# rev02_19.net
KiCad netlist of a schematic drawn in Altium Designer
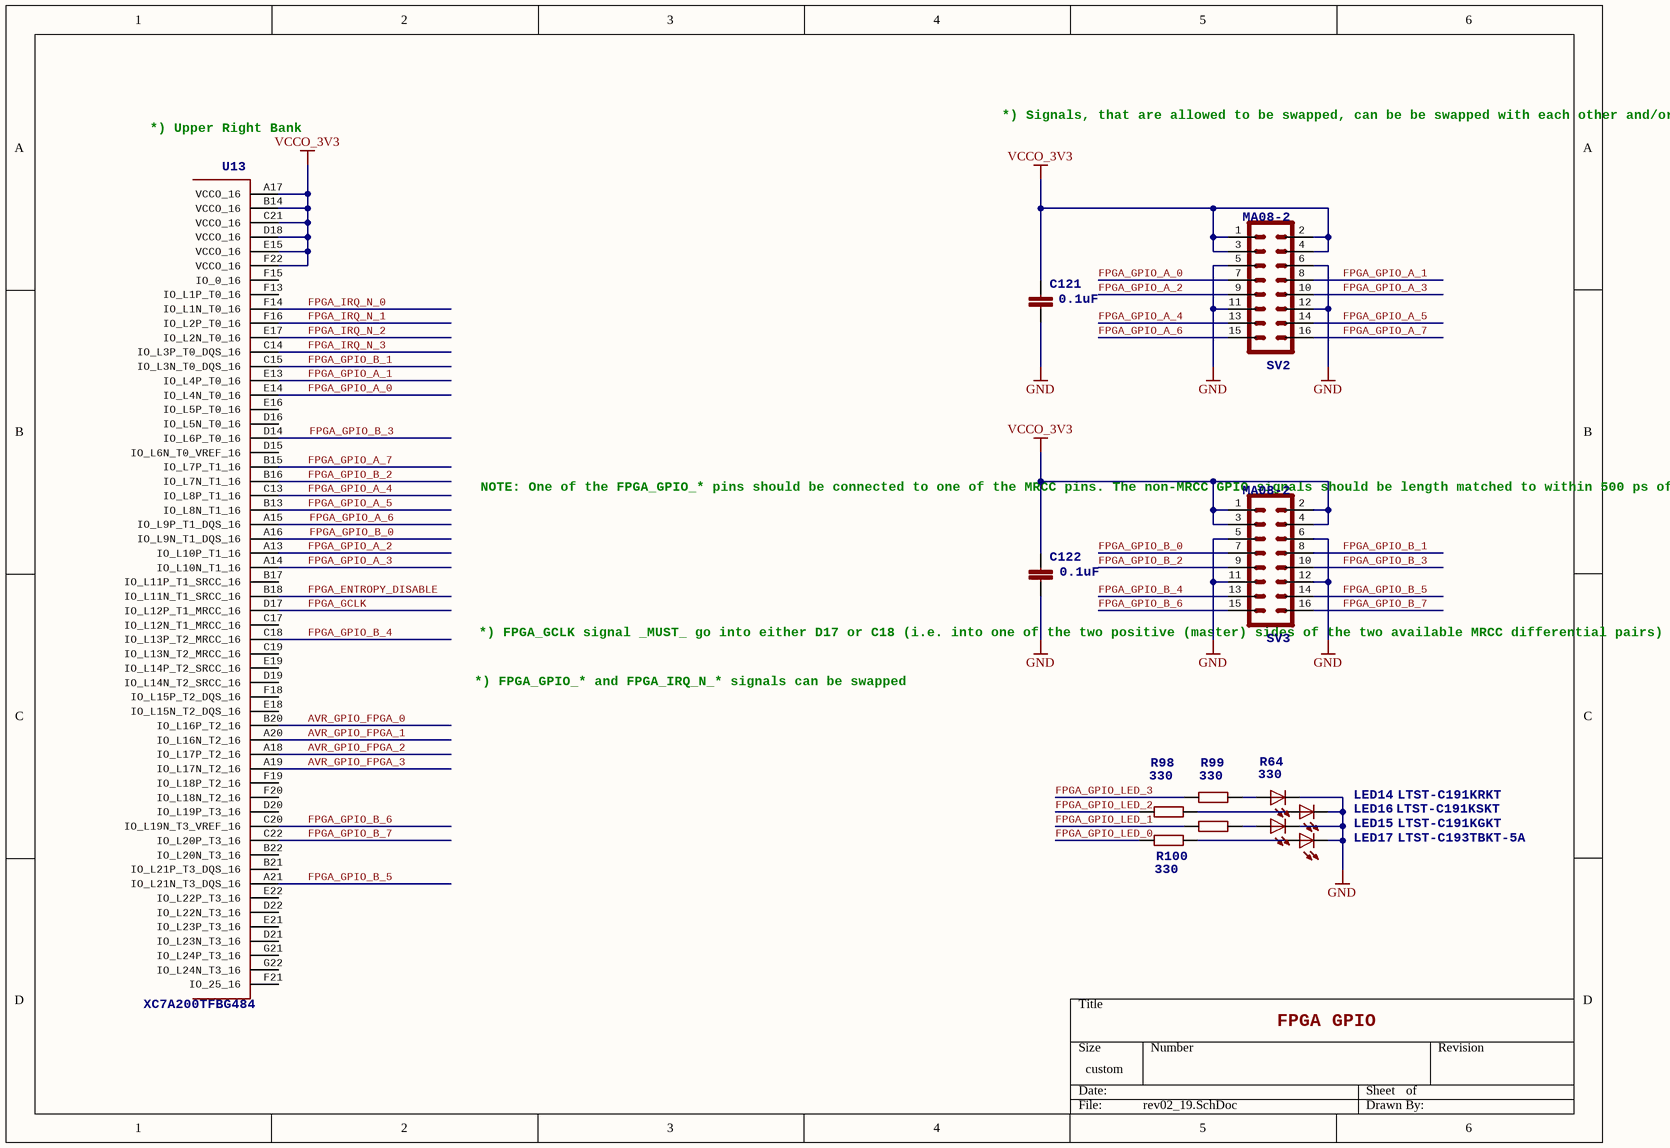
[diagram p0: rev02_19.SchDoc]

(export (version "E")
  (design (tool "Eeschema 10.0.6"))
  (components
    (comp (ref "C121")
      (value "0.1uF")
      (footprint "C_0402")
      (description "0402 CAPACITOR")
      (fields (field (name "TOLERANCE") "10%") (field (name ">NAME") "C121"))
      (libsource (lib "resistor") (part "C-EUC0402"))
    )
    (comp (ref "C122")
      (value "0.1uF")
      (footprint "C_0402")
      (description "0402 CAPACITOR")
      (fields (field (name "TOLERANCE") "10%") (field (name ">NAME") "C122"))
      (libsource (lib "resistor") (part "C-EUC0402"))
    )
    (comp (ref "LED14")
      (value "LTST-C191KRKT")
      (footprint "VD_0603")
      (description "RED LED")
      (libsource (lib "rev02_1") (part "LEDCHIP-LED0603"))
    )
    (comp (ref "LED15")
      (value "LTST-C191KGKT")
      (footprint "VD_0603")
      (description "GREEN LED")
      (libsource (lib "rev02_1") (part "LEDCHIP-LED0603"))
    )
    (comp (ref "LED16")
      (value "LTST-C191KSKT")
      (footprint "VD_0603")
      (description "YELLOW LED")
      (libsource (lib "rev02_1") (part "LEDCHIP-LED0603"))
    )
    (comp (ref "LED17")
      (value "LTST-C193TBKT-5A")
      (footprint "VD_0603")
      (description "BLUE LED")
      (libsource (lib "rev02_1") (part "LEDCHIP-LED0603"))
    )
    (comp (ref "R64")
      (value "330")
      (footprint "R_0402")
      (description "0402 Resistor 5%")
      (libsource (lib "resistor") (part "R-EU_R0402"))
    )
    (comp (ref "R98")
      (value "330")
      (footprint "R_0402")
      (description "0402 Resistor 5%")
      (libsource (lib "resistor") (part "R-EU_R0402"))
    )
    (comp (ref "R99")
      (value "330")
      (footprint "R_0402")
      (description "0402 Resistor 5%")
      (libsource (lib "resistor") (part "R-EU_R0402"))
    )
    (comp (ref "R100")
      (value "330")
      (footprint "R_0402")
      (description "0402 Resistor 5%")
      (libsource (lib "resistor") (part "R-EU_R0402"))
    )
    (comp (ref "SV2")
      (value "MA08-2")
      (footprint "PLD-16")
      (description "PIN HEADER 0.1\"")
      (fields (field (name ">VALUE") "MA08-2") (field (name ">NAME") "SV2"))
      (libsource (lib "con-lstb") (part "MA08-2"))
    )
    (comp (ref "SV3")
      (value "MA08-2")
      (footprint "PLD-16")
      (description "PIN HEADER 0.1\"")
      (fields (field (name ">VALUE") "MA08-2") (field (name ">NAME") "SV3"))
      (libsource (lib "con-lstb") (part "MA08-2"))
    )
    (comp (ref "U13")
      (value "XC7A200TFBG484")
      (footprint "BGA484C100P22X22_2300X2300X254")
      (description "Xilinx FPGA: XC7A200TFBG484")
      (fields
        (field (name "MFR") "Xilinx")
        (field (name "MPN") "XC7A200T-1FBG484C")
        (field (name ">NAME") "U13")
        (field (name ">VALUE") "XC7A200TFBG484")
      )
      (libsource (lib "Xilinx_XC7A200TFBG484") (part "XC7A200TFBG484"))
    )
  )
  (nets
    (net (code "1") (name "/AVR_GPIO_FPGA_0") (class "Default")
      (node (ref "U13") (pin "B20") (pinfunction "IO_L16P_T2_16_B20") (pintype "passive"))
    )
    (net (code "2") (name "/AVR_GPIO_FPGA_1") (class "Default")
      (node (ref "U13") (pin "A20") (pinfunction "IO_L16N_T2_16_A20") (pintype "passive"))
    )
    (net (code "3") (name "/AVR_GPIO_FPGA_2") (class "Default")
      (node (ref "U13") (pin "A18") (pinfunction "IO_L17P_T2_16_A18") (pintype "passive"))
    )
    (net (code "4") (name "/AVR_GPIO_FPGA_3") (class "Default")
      (node (ref "U13") (pin "A19") (pinfunction "IO_L17N_T2_16_A19") (pintype "passive"))
    )
    (net (code "5") (name "/FPGA_ENTROPY_DISABLE") (class "Default")
      (node (ref "U13") (pin "B18") (pinfunction "IO_L11N_T1_SRCC_16_B18") (pintype "passive"))
    )
    (net (code "6") (name "/FPGA_GCLK") (class "Default")
      (node (ref "U13") (pin "D17") (pinfunction "IO_L12P_T1_MRCC_16_D17") (pintype "passive"))
    )
    (net (code "7") (name "/FPGA_GPIO_A_0") (class "Default")
      (node (ref "SV2") (pin "7") (pinfunction "7_7") (pintype "passive"))
      (node (ref "U13") (pin "E14") (pinfunction "IO_L4N_T0_16_E14") (pintype "passive"))
    )
    (net (code "8") (name "/FPGA_GPIO_A_1") (class "Default")
      (node (ref "SV2") (pin "8") (pinfunction "8_8") (pintype "passive"))
      (node (ref "U13") (pin "E13") (pinfunction "IO_L4P_T0_16_E13") (pintype "passive"))
    )
    (net (code "9") (name "/FPGA_GPIO_A_2") (class "Default")
      (node (ref "SV2") (pin "9") (pinfunction "9_9") (pintype "passive"))
      (node (ref "U13") (pin "A13") (pinfunction "IO_L10P_T1_16_A13") (pintype "passive"))
    )
    (net (code "10") (name "/FPGA_GPIO_A_3") (class "Default")
      (node (ref "SV2") (pin "10") (pinfunction "10_10") (pintype "passive"))
      (node (ref "U13") (pin "A14") (pinfunction "IO_L10N_T1_16_A14") (pintype "passive"))
    )
    (net (code "11") (name "/FPGA_GPIO_A_4") (class "Default")
      (node (ref "SV2") (pin "13") (pinfunction "13_13") (pintype "passive"))
      (node (ref "U13") (pin "C13") (pinfunction "IO_L8P_T1_16_C13") (pintype "passive"))
    )
    (net (code "12") (name "/FPGA_GPIO_A_5") (class "Default")
      (node (ref "SV2") (pin "14") (pinfunction "14_14") (pintype "passive"))
      (node (ref "U13") (pin "B13") (pinfunction "IO_L8N_T1_16_B13") (pintype "passive"))
    )
    (net (code "13") (name "/FPGA_GPIO_A_6") (class "Default")
      (node (ref "SV2") (pin "15") (pinfunction "15_15") (pintype "passive"))
      (node (ref "U13") (pin "A15") (pinfunction "IO_L9P_T1_DQS_16_A15") (pintype "passive"))
    )
    (net (code "14") (name "/FPGA_GPIO_A_7") (class "Default")
      (node (ref "SV2") (pin "16") (pinfunction "16_16") (pintype "passive"))
      (node (ref "U13") (pin "B15") (pinfunction "IO_L7P_T1_16_B15") (pintype "passive"))
    )
    (net (code "15") (name "/FPGA_GPIO_B_0") (class "Default")
      (node (ref "SV3") (pin "7") (pinfunction "7_7") (pintype "passive"))
      (node (ref "U13") (pin "A16") (pinfunction "IO_L9N_T1_DQS_16_A16") (pintype "passive"))
    )
    (net (code "16") (name "/FPGA_GPIO_B_1") (class "Default")
      (node (ref "SV3") (pin "8") (pinfunction "8_8") (pintype "passive"))
      (node (ref "U13") (pin "C15") (pinfunction "IO_L3N_T0_DQS_16_C15") (pintype "passive"))
    )
    (net (code "17") (name "/FPGA_GPIO_B_2") (class "Default")
      (node (ref "SV3") (pin "9") (pinfunction "9_9") (pintype "passive"))
      (node (ref "U13") (pin "B16") (pinfunction "IO_L7N_T1_16_B16") (pintype "passive"))
    )
    (net (code "18") (name "/FPGA_GPIO_B_3") (class "Default")
      (node (ref "SV3") (pin "10") (pinfunction "10_10") (pintype "passive"))
      (node (ref "U13") (pin "D14") (pinfunction "IO_L6P_T0_16_D14") (pintype "passive"))
    )
    (net (code "19") (name "/FPGA_GPIO_B_4") (class "Default")
      (node (ref "SV3") (pin "13") (pinfunction "13_13") (pintype "passive"))
      (node (ref "U13") (pin "C18") (pinfunction "IO_L13P_T2_MRCC_16_C18") (pintype "passive"))
    )
    (net (code "20") (name "/FPGA_GPIO_B_5") (class "Default")
      (node (ref "SV3") (pin "14") (pinfunction "14_14") (pintype "passive"))
      (node (ref "U13") (pin "A21") (pinfunction "IO_L21N_T3_DQS_16_A21") (pintype "passive"))
    )
    (net (code "21") (name "/FPGA_GPIO_B_6") (class "Default")
      (node (ref "SV3") (pin "15") (pinfunction "15_15") (pintype "passive"))
      (node (ref "U13") (pin "C20") (pinfunction "IO_L19N_T3_VREF_16_C20") (pintype "passive"))
    )
    (net (code "22") (name "/FPGA_GPIO_B_7") (class "Default")
      (node (ref "SV3") (pin "16") (pinfunction "16_16") (pintype "passive"))
      (node (ref "U13") (pin "C22") (pinfunction "IO_L20P_T3_16_C22") (pintype "passive"))
    )
    (net (code "23") (name "/FPGA_GPIO_LED_0") (class "Default")
      (node (ref "R100") (pin "2") (pinfunction "2_2") (pintype "passive"))
    )
    (net (code "24") (name "/FPGA_GPIO_LED_1") (class "Default")
      (node (ref "R64") (pin "2") (pinfunction "2_2") (pintype "passive"))
    )
    (net (code "25") (name "/FPGA_GPIO_LED_2") (class "Default")
      (node (ref "R98") (pin "2") (pinfunction "2_2") (pintype "passive"))
    )
    (net (code "26") (name "/FPGA_GPIO_LED_3") (class "Default")
      (node (ref "R99") (pin "2") (pinfunction "2_2") (pintype "passive"))
    )
    (net (code "27") (name "/FPGA_IRQ_N_0") (class "Default")
      (node (ref "U13") (pin "F14") (pinfunction "IO_L1N_T0_16_F14") (pintype "passive"))
    )
    (net (code "28") (name "/FPGA_IRQ_N_1") (class "Default")
      (node (ref "U13") (pin "F16") (pinfunction "IO_L2P_T0_16_F16") (pintype "passive"))
    )
    (net (code "29") (name "/FPGA_IRQ_N_2") (class "Default")
      (node (ref "U13") (pin "E17") (pinfunction "IO_L2N_T0_16_E17") (pintype "passive"))
    )
    (net (code "30") (name "/FPGA_IRQ_N_3") (class "Default")
      (node (ref "U13") (pin "C14") (pinfunction "IO_L3P_T0_DQS_16_C14") (pintype "passive"))
    )
    (net (code "31") (name "GND") (class "Default")
      (node (ref "C121") (pin "2") (pinfunction "2_2") (pintype "passive"))
      (node (ref "C122") (pin "2") (pinfunction "2_2") (pintype "passive"))
      (node (ref "LED14") (pin "2") (pinfunction "C_2") (pintype "passive"))
      (node (ref "LED15") (pin "2") (pinfunction "C_2") (pintype "passive"))
      (node (ref "LED16") (pin "2") (pinfunction "C_2") (pintype "passive"))
      (node (ref "LED17") (pin "2") (pinfunction "C_2") (pintype "passive"))
      (node (ref "SV2") (pin "11") (pinfunction "11_11") (pintype "passive"))
      (node (ref "SV2") (pin "12") (pinfunction "12_12") (pintype "passive"))
      (node (ref "SV2") (pin "5") (pinfunction "5_5") (pintype "passive"))
      (node (ref "SV2") (pin "6") (pinfunction "6_6") (pintype "passive"))
      (node (ref "SV3") (pin "11") (pinfunction "11_11") (pintype "passive"))
      (node (ref "SV3") (pin "12") (pinfunction "12_12") (pintype "passive"))
      (node (ref "SV3") (pin "5") (pinfunction "5_5") (pintype "passive"))
      (node (ref "SV3") (pin "6") (pinfunction "6_6") (pintype "passive"))
    )
    (net (code "32") (name "Net-(LED14-A)") (class "Default")
      (node (ref "LED14") (pin "1") (pinfunction "A_1") (pintype "passive"))
      (node (ref "R99") (pin "1") (pinfunction "1_1") (pintype "passive"))
    )
    (net (code "33") (name "Net-(LED15-A)") (class "Default")
      (node (ref "LED15") (pin "1") (pinfunction "A_1") (pintype "passive"))
      (node (ref "R64") (pin "1") (pinfunction "1_1") (pintype "passive"))
    )
    (net (code "34") (name "Net-(LED16-A)") (class "Default")
      (node (ref "LED16") (pin "1") (pinfunction "A_1") (pintype "passive"))
      (node (ref "R98") (pin "1") (pinfunction "1_1") (pintype "passive"))
    )
    (net (code "35") (name "Net-(LED17-A)") (class "Default")
      (node (ref "LED17") (pin "1") (pinfunction "A_1") (pintype "passive"))
      (node (ref "R100") (pin "1") (pinfunction "1_1") (pintype "passive"))
    )
    (net (code "36") (name "VCCO_3V3") (class "Default")
      (node (ref "C121") (pin "1") (pinfunction "1_1") (pintype "passive"))
      (node (ref "C122") (pin "1") (pinfunction "1_1") (pintype "passive"))
      (node (ref "SV2") (pin "1") (pinfunction "1_1") (pintype "passive"))
      (node (ref "SV2") (pin "2") (pinfunction "2_2") (pintype "passive"))
      (node (ref "SV2") (pin "3") (pinfunction "3_3") (pintype "passive"))
      (node (ref "SV2") (pin "4") (pinfunction "4_4") (pintype "passive"))
      (node (ref "SV3") (pin "1") (pinfunction "1_1") (pintype "passive"))
      (node (ref "SV3") (pin "2") (pinfunction "2_2") (pintype "passive"))
      (node (ref "SV3") (pin "3") (pinfunction "3_3") (pintype "passive"))
      (node (ref "SV3") (pin "4") (pinfunction "4_4") (pintype "passive"))
      (node (ref "U13") (pin "A17") (pinfunction "VCCO_16_A17") (pintype "passive"))
      (node (ref "U13") (pin "B14") (pinfunction "VCCO_16_B14") (pintype "passive"))
      (node (ref "U13") (pin "C21") (pinfunction "VCCO_16_C21") (pintype "passive"))
      (node (ref "U13") (pin "D18") (pinfunction "VCCO_16_D18") (pintype "passive"))
      (node (ref "U13") (pin "E15") (pinfunction "VCCO_16_E15") (pintype "passive"))
      (node (ref "U13") (pin "F22") (pinfunction "VCCO_16_F22") (pintype "passive"))
    )
    (net (code "37") (name "unconnected-(U13E-IO_0_16-PadF15)") (class "Default")
      (node (ref "U13") (pin "F15") (pinfunction "IO_0_16_F15") (pintype "passive"))
    )
    (net (code "38") (name "unconnected-(U13E-IO_25_16-PadF21)") (class "Default")
      (node (ref "U13") (pin "F21") (pinfunction "IO_25_16_F21") (pintype "passive"))
    )
    (net (code "39") (name "unconnected-(U13E-IO_L1P_T0_16-PadF13)") (class "Default")
      (node (ref "U13") (pin "F13") (pinfunction "IO_L1P_T0_16_F13") (pintype "passive"))
    )
    (net (code "40") (name "unconnected-(U13E-IO_L5N_T0_16-PadD16)") (class "Default")
      (node (ref "U13") (pin "D16") (pinfunction "IO_L5N_T0_16_D16") (pintype "passive"))
    )
    (net (code "41") (name "unconnected-(U13E-IO_L5P_T0_16-PadE16)") (class "Default")
      (node (ref "U13") (pin "E16") (pinfunction "IO_L5P_T0_16_E16") (pintype "passive"))
    )
    (net (code "42") (name "unconnected-(U13E-IO_L6N_T0_VREF_16-PadD15)") (class "Default")
      (node (ref "U13") (pin "D15") (pinfunction "IO_L6N_T0_VREF_16_D15") (pintype "passive"))
    )
    (net (code "43") (name "unconnected-(U13E-IO_L11P_T1_SRCC_16-PadB17)") (class "Default")
      (node (ref "U13") (pin "B17") (pinfunction "IO_L11P_T1_SRCC_16_B17") (pintype "passive"))
    )
    (net (code "44") (name "unconnected-(U13E-IO_L12N_T1_MRCC_16-PadC17)") (class "Default")
      (node (ref "U13") (pin "C17") (pinfunction "IO_L12N_T1_MRCC_16_C17") (pintype "passive"))
    )
    (net (code "45") (name "unconnected-(U13E-IO_L13N_T2_MRCC_16-PadC19)") (class "Default")
      (node (ref "U13") (pin "C19") (pinfunction "IO_L13N_T2_MRCC_16_C19") (pintype "passive"))
    )
    (net (code "46") (name "unconnected-(U13E-IO_L14N_T2_SRCC_16-PadD19)") (class "Default")
      (node (ref "U13") (pin "D19") (pinfunction "IO_L14N_T2_SRCC_16_D19") (pintype "passive"))
    )
    (net (code "47") (name "unconnected-(U13E-IO_L14P_T2_SRCC_16-PadE19)") (class "Default")
      (node (ref "U13") (pin "E19") (pinfunction "IO_L14P_T2_SRCC_16_E19") (pintype "passive"))
    )
    (net (code "48") (name "unconnected-(U13E-IO_L15N_T2_DQS_16-PadE18)") (class "Default")
      (node (ref "U13") (pin "E18") (pinfunction "IO_L15N_T2_DQS_16_E18") (pintype "passive"))
    )
    (net (code "49") (name "unconnected-(U13E-IO_L15P_T2_DQS_16-PadF18)") (class "Default")
      (node (ref "U13") (pin "F18") (pinfunction "IO_L15P_T2_DQS_16_F18") (pintype "passive"))
    )
    (net (code "50") (name "unconnected-(U13E-IO_L18N_T2_16-PadF20)") (class "Default")
      (node (ref "U13") (pin "F20") (pinfunction "IO_L18N_T2_16_F20") (pintype "passive"))
    )
    (net (code "51") (name "unconnected-(U13E-IO_L18P_T2_16-PadF19)") (class "Default")
      (node (ref "U13") (pin "F19") (pinfunction "IO_L18P_T2_16_F19") (pintype "passive"))
    )
    (net (code "52") (name "unconnected-(U13E-IO_L19P_T3_16-PadD20)") (class "Default")
      (node (ref "U13") (pin "D20") (pinfunction "IO_L19P_T3_16_D20") (pintype "passive"))
    )
    (net (code "53") (name "unconnected-(U13E-IO_L20N_T3_16-PadB22)") (class "Default")
      (node (ref "U13") (pin "B22") (pinfunction "IO_L20N_T3_16_B22") (pintype "passive"))
    )
    (net (code "54") (name "unconnected-(U13E-IO_L21P_T3_DQS_16-PadB21)") (class "Default")
      (node (ref "U13") (pin "B21") (pinfunction "IO_L21P_T3_DQS_16_B21") (pintype "passive"))
    )
    (net (code "55") (name "unconnected-(U13E-IO_L22N_T3_16-PadD22)") (class "Default")
      (node (ref "U13") (pin "D22") (pinfunction "IO_L22N_T3_16_D22") (pintype "passive"))
    )
    (net (code "56") (name "unconnected-(U13E-IO_L22P_T3_16-PadE22)") (class "Default")
      (node (ref "U13") (pin "E22") (pinfunction "IO_L22P_T3_16_E22") (pintype "passive"))
    )
    (net (code "57") (name "unconnected-(U13E-IO_L23N_T3_16-PadD21)") (class "Default")
      (node (ref "U13") (pin "D21") (pinfunction "IO_L23N_T3_16_D21") (pintype "passive"))
    )
    (net (code "58") (name "unconnected-(U13E-IO_L23P_T3_16-PadE21)") (class "Default")
      (node (ref "U13") (pin "E21") (pinfunction "IO_L23P_T3_16_E21") (pintype "passive"))
    )
    (net (code "59") (name "unconnected-(U13E-IO_L24N_T3_16-PadG22)") (class "Default")
      (node (ref "U13") (pin "G22") (pinfunction "IO_L24N_T3_16_G22") (pintype "passive"))
    )
    (net (code "60") (name "unconnected-(U13E-IO_L24P_T3_16-PadG21)") (class "Default")
      (node (ref "U13") (pin "G21") (pinfunction "IO_L24P_T3_16_G21") (pintype "passive"))
    )
  )
)
